# iPhone11ProMaxNEI.net
KiCad netlist of a schematic drawn in Altium Designer
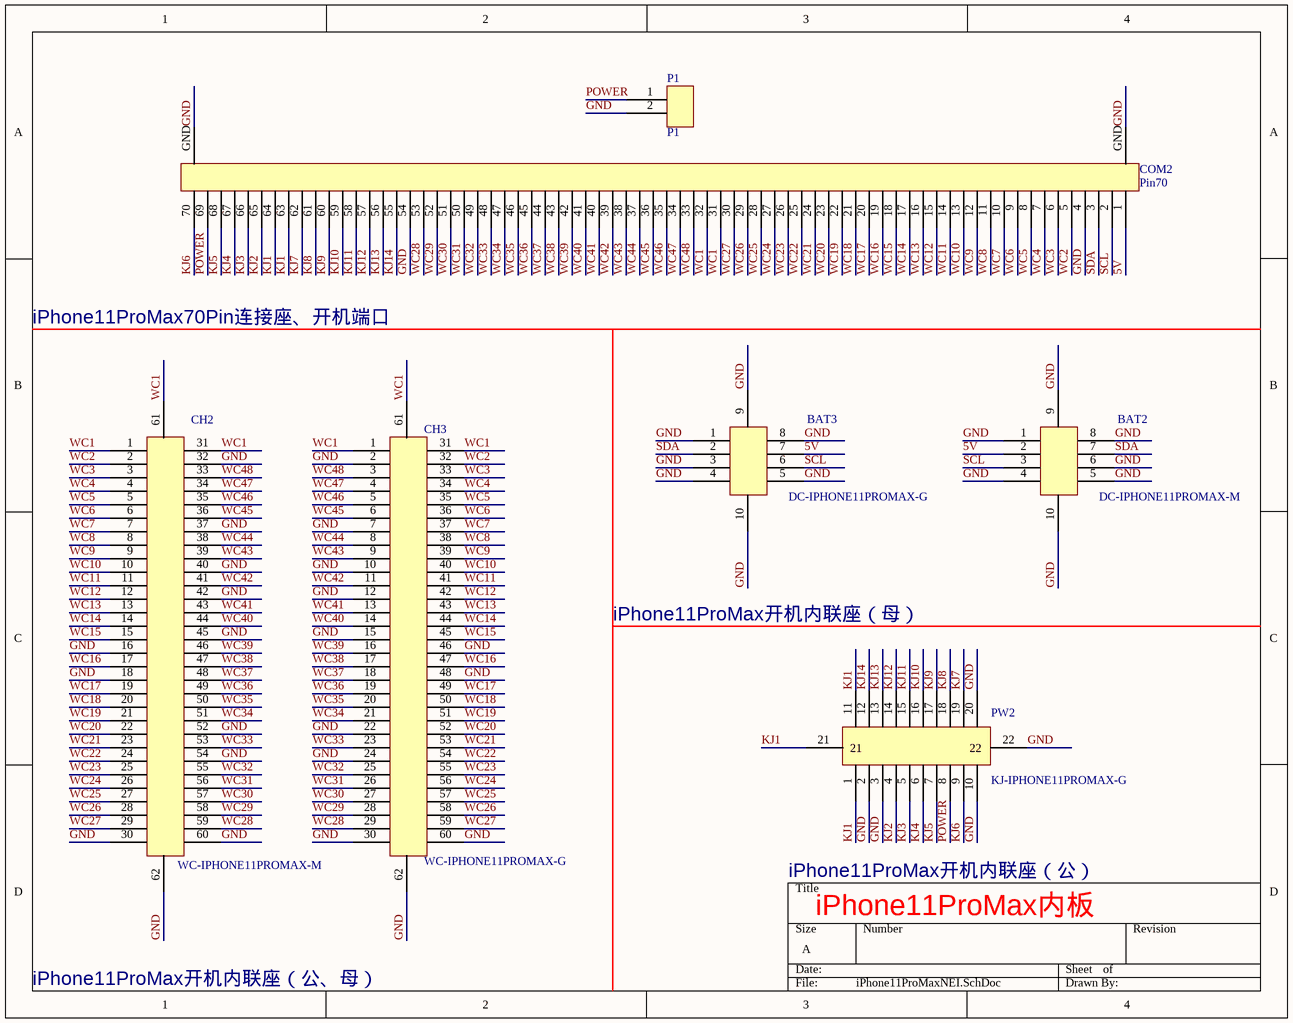
[diagram p0: iPhone11ProMaxNEI.SchDoc]

(export (version "E")
  (design (tool "Eeschema 10.0.6"))
  (components
    (comp (ref "BAT2")
      (value "DC-IPHONE11PROMAX-M")
      (footprint "IPHONE11-WXCD-M")
      (libsource (lib "iPhone") (part "WXCD-IPHONE11-M"))
    )
    (comp (ref "BAT3")
      (value "DC-IPHONE11PROMAX-G")
      (footprint "IPHONE11-WXCD-G")
      (libsource (lib "iPhone") (part "WXCD-IPHONE11-M"))
    )
    (comp (ref "CH2")
      (value "WC-IPHONE11PROMAX-M")
      (footprint "IPHONE11PROMAX-WC-M")
      (libsource (lib "iPhone") (part "WC-IPHONE11PROMAX-M"))
    )
    (comp (ref "CH3")
      (value "WC-IPHONE11PROMAX-G")
      (footprint "IPHONE11PROMAX-WC-G")
      (libsource (lib "iPhone") (part "WC-IPHONE11PROMAX-G"))
    )
    (comp (ref "COM2") (value "Pin70") (footprint "Pin70") (libsource (lib "iPhone") (part "Pin70")))
    (comp (ref "P1") (value "P1") (footprint "P-2") (libsource (lib "iPhone") (part "P1")))
    (comp (ref "PW2")
      (value "KJ-IPHONE11PROMAX-G")
      (footprint "IPHONE11PROMAX-KJ-G")
      (libsource (lib "iPhone") (part "KJ-IPHONE11PROMAX-G"))
    )
  )
  (nets
    (net (code "1") (name "/5V") (class "Default")
      (node (ref "BAT2") (pin "2") (pintype "passive"))
      (node (ref "BAT3") (pin "7") (pintype "passive"))
      (node (ref "COM2") (pin "1") (pintype "passive"))
    )
    (net (code "2") (name "/GND") (class "Default")
      (node (ref "BAT2") (pin "1") (pintype "passive"))
      (node (ref "BAT2") (pin "10") (pintype "passive"))
      (node (ref "BAT2") (pin "4") (pintype "passive"))
      (node (ref "BAT2") (pin "5") (pintype "passive"))
      (node (ref "BAT2") (pin "6") (pintype "passive"))
      (node (ref "BAT2") (pin "8") (pintype "passive"))
      (node (ref "BAT2") (pin "9") (pintype "passive"))
      (node (ref "BAT3") (pin "1") (pintype "passive"))
      (node (ref "BAT3") (pin "10") (pintype "passive"))
      (node (ref "BAT3") (pin "3") (pintype "passive"))
      (node (ref "BAT3") (pin "4") (pintype "passive"))
      (node (ref "BAT3") (pin "5") (pintype "passive"))
      (node (ref "BAT3") (pin "8") (pintype "passive"))
      (node (ref "BAT3") (pin "9") (pintype "passive"))
      (node (ref "CH2") (pin "16") (pintype "passive"))
      (node (ref "CH2") (pin "18") (pintype "passive"))
      (node (ref "CH2") (pin "30") (pintype "passive"))
      (node (ref "CH2") (pin "32") (pintype "passive"))
      (node (ref "CH2") (pin "37") (pintype "passive"))
      (node (ref "CH2") (pin "40") (pintype "passive"))
      (node (ref "CH2") (pin "42") (pintype "passive"))
      (node (ref "CH2") (pin "45") (pintype "passive"))
      (node (ref "CH2") (pin "52") (pintype "passive"))
      (node (ref "CH2") (pin "54") (pintype "passive"))
      (node (ref "CH2") (pin "60") (pintype "passive"))
      (node (ref "CH2") (pin "62") (pintype "passive"))
      (node (ref "CH3") (pin "10") (pintype "passive"))
      (node (ref "CH3") (pin "12") (pintype "passive"))
      (node (ref "CH3") (pin "15") (pintype "passive"))
      (node (ref "CH3") (pin "2") (pintype "passive"))
      (node (ref "CH3") (pin "22") (pintype "passive"))
      (node (ref "CH3") (pin "24") (pintype "passive"))
      (node (ref "CH3") (pin "30") (pintype "passive"))
      (node (ref "CH3") (pin "46") (pintype "passive"))
      (node (ref "CH3") (pin "48") (pintype "passive"))
      (node (ref "CH3") (pin "60") (pintype "passive"))
      (node (ref "CH3") (pin "62") (pintype "passive"))
      (node (ref "CH3") (pin "7") (pintype "passive"))
      (node (ref "COM2") (pin "4") (pintype "passive"))
      (node (ref "COM2") (pin "54") (pintype "passive"))
      (node (ref "COM2") (pin "GND") (pintype "passive"))
      (node (ref "P1") (pin "2") (pintype "passive"))
      (node (ref "PW2") (pin "10") (pintype "passive"))
      (node (ref "PW2") (pin "2") (pintype "passive"))
      (node (ref "PW2") (pin "20") (pintype "passive"))
      (node (ref "PW2") (pin "22") (pinfunction "22_22") (pintype "passive"))
      (node (ref "PW2") (pin "3") (pintype "passive"))
    )
    (net (code "3") (name "/KJ1") (class "Default")
      (node (ref "COM2") (pin "63") (pintype "passive"))
      (node (ref "COM2") (pin "64") (pintype "passive"))
      (node (ref "PW2") (pin "1") (pintype "passive"))
      (node (ref "PW2") (pin "11") (pintype "passive"))
      (node (ref "PW2") (pin "21") (pinfunction "21_21") (pintype "passive"))
    )
    (net (code "4") (name "/KJ2") (class "Default")
      (node (ref "COM2") (pin "65") (pintype "passive"))
      (node (ref "PW2") (pin "4") (pintype "passive"))
    )
    (net (code "5") (name "/KJ3") (class "Default")
      (node (ref "COM2") (pin "66") (pintype "passive"))
      (node (ref "PW2") (pin "5") (pintype "passive"))
    )
    (net (code "6") (name "/KJ4") (class "Default")
      (node (ref "COM2") (pin "67") (pintype "passive"))
      (node (ref "PW2") (pin "6") (pintype "passive"))
    )
    (net (code "7") (name "/KJ5") (class "Default")
      (node (ref "COM2") (pin "68") (pintype "passive"))
      (node (ref "PW2") (pin "7") (pintype "passive"))
    )
    (net (code "8") (name "/KJ6") (class "Default")
      (node (ref "COM2") (pin "70") (pintype "passive"))
      (node (ref "PW2") (pin "9") (pintype "passive"))
    )
    (net (code "9") (name "/KJ7") (class "Default")
      (node (ref "COM2") (pin "62") (pintype "passive"))
      (node (ref "PW2") (pin "19") (pintype "passive"))
    )
    (net (code "10") (name "/KJ8") (class "Default")
      (node (ref "COM2") (pin "61") (pintype "passive"))
      (node (ref "PW2") (pin "18") (pintype "passive"))
    )
    (net (code "11") (name "/KJ9") (class "Default")
      (node (ref "COM2") (pin "60") (pintype "passive"))
      (node (ref "PW2") (pin "17") (pintype "passive"))
    )
    (net (code "12") (name "/KJ10") (class "Default")
      (node (ref "COM2") (pin "59") (pintype "passive"))
      (node (ref "PW2") (pin "16") (pintype "passive"))
    )
    (net (code "13") (name "/KJ11") (class "Default")
      (node (ref "COM2") (pin "58") (pintype "passive"))
      (node (ref "PW2") (pin "15") (pintype "passive"))
    )
    (net (code "14") (name "/KJ12") (class "Default")
      (node (ref "COM2") (pin "57") (pintype "passive"))
      (node (ref "PW2") (pin "14") (pintype "passive"))
    )
    (net (code "15") (name "/KJ13") (class "Default")
      (node (ref "COM2") (pin "56") (pintype "passive"))
      (node (ref "PW2") (pin "13") (pintype "passive"))
    )
    (net (code "16") (name "/KJ14") (class "Default")
      (node (ref "COM2") (pin "55") (pintype "passive"))
      (node (ref "PW2") (pin "12") (pintype "passive"))
    )
    (net (code "17") (name "/POWER") (class "Default")
      (node (ref "COM2") (pin "69") (pintype "passive"))
      (node (ref "P1") (pin "1") (pintype "passive"))
      (node (ref "PW2") (pin "8") (pintype "passive"))
    )
    (net (code "18") (name "/SCL") (class "Default")
      (node (ref "BAT2") (pin "3") (pintype "passive"))
      (node (ref "BAT3") (pin "6") (pintype "passive"))
      (node (ref "COM2") (pin "2") (pintype "passive"))
    )
    (net (code "19") (name "/SDA") (class "Default")
      (node (ref "BAT2") (pin "7") (pintype "passive"))
      (node (ref "BAT3") (pin "2") (pintype "passive"))
      (node (ref "COM2") (pin "3") (pintype "passive"))
    )
    (net (code "20") (name "/WC1") (class "Default")
      (node (ref "CH2") (pin "1") (pintype "passive"))
      (node (ref "CH2") (pin "31") (pintype "passive"))
      (node (ref "CH2") (pin "61") (pintype "passive"))
      (node (ref "CH3") (pin "1") (pintype "passive"))
      (node (ref "CH3") (pin "31") (pintype "passive"))
      (node (ref "CH3") (pin "61") (pintype "passive"))
      (node (ref "COM2") (pin "31") (pintype "passive"))
      (node (ref "COM2") (pin "32") (pintype "passive"))
    )
    (net (code "21") (name "/WC2") (class "Default")
      (node (ref "CH2") (pin "2") (pintype "passive"))
      (node (ref "CH3") (pin "32") (pintype "passive"))
      (node (ref "COM2") (pin "5") (pintype "passive"))
    )
    (net (code "22") (name "/WC3") (class "Default")
      (node (ref "CH2") (pin "3") (pintype "passive"))
      (node (ref "CH3") (pin "33") (pintype "passive"))
      (node (ref "COM2") (pin "6") (pintype "passive"))
    )
    (net (code "23") (name "/WC4") (class "Default")
      (node (ref "CH2") (pin "4") (pintype "passive"))
      (node (ref "CH3") (pin "34") (pintype "passive"))
      (node (ref "COM2") (pin "7") (pintype "passive"))
    )
    (net (code "24") (name "/WC5") (class "Default")
      (node (ref "CH2") (pin "5") (pintype "passive"))
      (node (ref "CH3") (pin "35") (pintype "passive"))
      (node (ref "COM2") (pin "8") (pintype "passive"))
    )
    (net (code "25") (name "/WC6") (class "Default")
      (node (ref "CH2") (pin "6") (pintype "passive"))
      (node (ref "CH3") (pin "36") (pintype "passive"))
      (node (ref "COM2") (pin "9") (pintype "passive"))
    )
    (net (code "26") (name "/WC7") (class "Default")
      (node (ref "CH2") (pin "7") (pintype "passive"))
      (node (ref "CH3") (pin "37") (pintype "passive"))
      (node (ref "COM2") (pin "10") (pintype "passive"))
    )
    (net (code "27") (name "/WC8") (class "Default")
      (node (ref "CH2") (pin "8") (pintype "passive"))
      (node (ref "CH3") (pin "38") (pintype "passive"))
      (node (ref "COM2") (pin "11") (pintype "passive"))
    )
    (net (code "28") (name "/WC9") (class "Default")
      (node (ref "CH2") (pin "9") (pintype "passive"))
      (node (ref "CH3") (pin "39") (pintype "passive"))
      (node (ref "COM2") (pin "12") (pintype "passive"))
    )
    (net (code "29") (name "/WC10") (class "Default")
      (node (ref "CH2") (pin "10") (pintype "passive"))
      (node (ref "CH3") (pin "40") (pintype "passive"))
      (node (ref "COM2") (pin "13") (pintype "passive"))
    )
    (net (code "30") (name "/WC11") (class "Default")
      (node (ref "CH2") (pin "11") (pintype "passive"))
      (node (ref "CH3") (pin "41") (pintype "passive"))
      (node (ref "COM2") (pin "14") (pintype "passive"))
    )
    (net (code "31") (name "/WC12") (class "Default")
      (node (ref "CH2") (pin "12") (pintype "passive"))
      (node (ref "CH3") (pin "42") (pintype "passive"))
      (node (ref "COM2") (pin "15") (pintype "passive"))
    )
    (net (code "32") (name "/WC13") (class "Default")
      (node (ref "CH2") (pin "13") (pintype "passive"))
      (node (ref "CH3") (pin "43") (pintype "passive"))
      (node (ref "COM2") (pin "16") (pintype "passive"))
    )
    (net (code "33") (name "/WC14") (class "Default")
      (node (ref "CH2") (pin "14") (pintype "passive"))
      (node (ref "CH3") (pin "44") (pintype "passive"))
      (node (ref "COM2") (pin "17") (pintype "passive"))
    )
    (net (code "34") (name "/WC15") (class "Default")
      (node (ref "CH2") (pin "15") (pintype "passive"))
      (node (ref "CH3") (pin "45") (pintype "passive"))
      (node (ref "COM2") (pin "18") (pintype "passive"))
    )
    (net (code "35") (name "/WC16") (class "Default")
      (node (ref "CH2") (pin "17") (pintype "passive"))
      (node (ref "CH3") (pin "47") (pintype "passive"))
      (node (ref "COM2") (pin "19") (pintype "passive"))
    )
    (net (code "36") (name "/WC17") (class "Default")
      (node (ref "CH2") (pin "19") (pintype "passive"))
      (node (ref "CH3") (pin "49") (pintype "passive"))
      (node (ref "COM2") (pin "20") (pintype "passive"))
    )
    (net (code "37") (name "/WC18") (class "Default")
      (node (ref "CH2") (pin "20") (pintype "passive"))
      (node (ref "CH3") (pin "50") (pintype "passive"))
      (node (ref "COM2") (pin "21") (pintype "passive"))
    )
    (net (code "38") (name "/WC19") (class "Default")
      (node (ref "CH2") (pin "21") (pintype "passive"))
      (node (ref "CH3") (pin "51") (pintype "passive"))
      (node (ref "COM2") (pin "22") (pintype "passive"))
    )
    (net (code "39") (name "/WC20") (class "Default")
      (node (ref "CH2") (pin "22") (pintype "passive"))
      (node (ref "CH3") (pin "52") (pintype "passive"))
      (node (ref "COM2") (pin "23") (pintype "passive"))
    )
    (net (code "40") (name "/WC21") (class "Default")
      (node (ref "CH2") (pin "23") (pintype "passive"))
      (node (ref "CH3") (pin "53") (pintype "passive"))
      (node (ref "COM2") (pin "24") (pintype "passive"))
    )
    (net (code "41") (name "/WC22") (class "Default")
      (node (ref "CH2") (pin "24") (pintype "passive"))
      (node (ref "CH3") (pin "54") (pintype "passive"))
      (node (ref "COM2") (pin "25") (pintype "passive"))
    )
    (net (code "42") (name "/WC23") (class "Default")
      (node (ref "CH2") (pin "25") (pintype "passive"))
      (node (ref "CH3") (pin "55") (pintype "passive"))
      (node (ref "COM2") (pin "26") (pintype "passive"))
    )
    (net (code "43") (name "/WC24") (class "Default")
      (node (ref "CH2") (pin "26") (pintype "passive"))
      (node (ref "CH3") (pin "56") (pintype "passive"))
      (node (ref "COM2") (pin "27") (pintype "passive"))
    )
    (net (code "44") (name "/WC25") (class "Default")
      (node (ref "CH2") (pin "27") (pintype "passive"))
      (node (ref "CH3") (pin "57") (pintype "passive"))
      (node (ref "COM2") (pin "28") (pintype "passive"))
    )
    (net (code "45") (name "/WC26") (class "Default")
      (node (ref "CH2") (pin "28") (pintype "passive"))
      (node (ref "CH3") (pin "58") (pintype "passive"))
      (node (ref "COM2") (pin "29") (pintype "passive"))
    )
    (net (code "46") (name "/WC27") (class "Default")
      (node (ref "CH2") (pin "29") (pintype "passive"))
      (node (ref "CH3") (pin "59") (pintype "passive"))
      (node (ref "COM2") (pin "30") (pintype "passive"))
    )
    (net (code "47") (name "/WC28") (class "Default")
      (node (ref "CH2") (pin "59") (pintype "passive"))
      (node (ref "CH3") (pin "29") (pintype "passive"))
      (node (ref "COM2") (pin "53") (pintype "passive"))
    )
    (net (code "48") (name "/WC29") (class "Default")
      (node (ref "CH2") (pin "58") (pintype "passive"))
      (node (ref "CH3") (pin "28") (pintype "passive"))
      (node (ref "COM2") (pin "52") (pintype "passive"))
    )
    (net (code "49") (name "/WC30") (class "Default")
      (node (ref "CH2") (pin "57") (pintype "passive"))
      (node (ref "CH3") (pin "27") (pintype "passive"))
      (node (ref "COM2") (pin "51") (pintype "passive"))
    )
    (net (code "50") (name "/WC31") (class "Default")
      (node (ref "CH2") (pin "56") (pintype "passive"))
      (node (ref "CH3") (pin "26") (pintype "passive"))
      (node (ref "COM2") (pin "50") (pintype "passive"))
    )
    (net (code "51") (name "/WC32") (class "Default")
      (node (ref "CH2") (pin "55") (pintype "passive"))
      (node (ref "CH3") (pin "25") (pintype "passive"))
      (node (ref "COM2") (pin "49") (pintype "passive"))
    )
    (net (code "52") (name "/WC33") (class "Default")
      (node (ref "CH2") (pin "53") (pintype "passive"))
      (node (ref "CH3") (pin "23") (pintype "passive"))
      (node (ref "COM2") (pin "48") (pintype "passive"))
    )
    (net (code "53") (name "/WC34") (class "Default")
      (node (ref "CH2") (pin "51") (pintype "passive"))
      (node (ref "CH3") (pin "21") (pintype "passive"))
      (node (ref "COM2") (pin "47") (pintype "passive"))
    )
    (net (code "54") (name "/WC35") (class "Default")
      (node (ref "CH2") (pin "50") (pintype "passive"))
      (node (ref "CH3") (pin "20") (pintype "passive"))
      (node (ref "COM2") (pin "46") (pintype "passive"))
    )
    (net (code "55") (name "/WC36") (class "Default")
      (node (ref "CH2") (pin "49") (pintype "passive"))
      (node (ref "CH3") (pin "19") (pintype "passive"))
      (node (ref "COM2") (pin "45") (pintype "passive"))
    )
    (net (code "56") (name "/WC37") (class "Default")
      (node (ref "CH2") (pin "48") (pintype "passive"))
      (node (ref "CH3") (pin "18") (pintype "passive"))
      (node (ref "COM2") (pin "44") (pintype "passive"))
    )
    (net (code "57") (name "/WC38") (class "Default")
      (node (ref "CH2") (pin "47") (pintype "passive"))
      (node (ref "CH3") (pin "17") (pintype "passive"))
      (node (ref "COM2") (pin "43") (pintype "passive"))
    )
    (net (code "58") (name "/WC39") (class "Default")
      (node (ref "CH2") (pin "46") (pintype "passive"))
      (node (ref "CH3") (pin "16") (pintype "passive"))
      (node (ref "COM2") (pin "42") (pintype "passive"))
    )
    (net (code "59") (name "/WC40") (class "Default")
      (node (ref "CH2") (pin "44") (pintype "passive"))
      (node (ref "CH3") (pin "14") (pintype "passive"))
      (node (ref "COM2") (pin "41") (pintype "passive"))
    )
    (net (code "60") (name "/WC41") (class "Default")
      (node (ref "CH2") (pin "43") (pintype "passive"))
      (node (ref "CH3") (pin "13") (pintype "passive"))
      (node (ref "COM2") (pin "40") (pintype "passive"))
    )
    (net (code "61") (name "/WC42") (class "Default")
      (node (ref "CH2") (pin "41") (pintype "passive"))
      (node (ref "CH3") (pin "11") (pintype "passive"))
      (node (ref "COM2") (pin "39") (pintype "passive"))
    )
    (net (code "62") (name "/WC43") (class "Default")
      (node (ref "CH2") (pin "39") (pintype "passive"))
      (node (ref "CH3") (pin "9") (pintype "passive"))
      (node (ref "COM2") (pin "38") (pintype "passive"))
    )
    (net (code "63") (name "/WC44") (class "Default")
      (node (ref "CH2") (pin "38") (pintype "passive"))
      (node (ref "CH3") (pin "8") (pintype "passive"))
      (node (ref "COM2") (pin "37") (pintype "passive"))
    )
    (net (code "64") (name "/WC45") (class "Default")
      (node (ref "CH2") (pin "36") (pintype "passive"))
      (node (ref "CH3") (pin "6") (pintype "passive"))
      (node (ref "COM2") (pin "36") (pintype "passive"))
    )
    (net (code "65") (name "/WC46") (class "Default")
      (node (ref "CH2") (pin "35") (pintype "passive"))
      (node (ref "CH3") (pin "5") (pintype "passive"))
      (node (ref "COM2") (pin "35") (pintype "passive"))
    )
    (net (code "66") (name "/WC47") (class "Default")
      (node (ref "CH2") (pin "34") (pintype "passive"))
      (node (ref "CH3") (pin "4") (pintype "passive"))
      (node (ref "COM2") (pin "34") (pintype "passive"))
    )
    (net (code "67") (name "/WC48") (class "Default")
      (node (ref "CH2") (pin "33") (pintype "passive"))
      (node (ref "CH3") (pin "3") (pintype "passive"))
      (node (ref "COM2") (pin "33") (pintype "passive"))
    )
  )
)
